# USB-SERIAL.net
KiCad netlist of a schematic drawn in Altium Designer
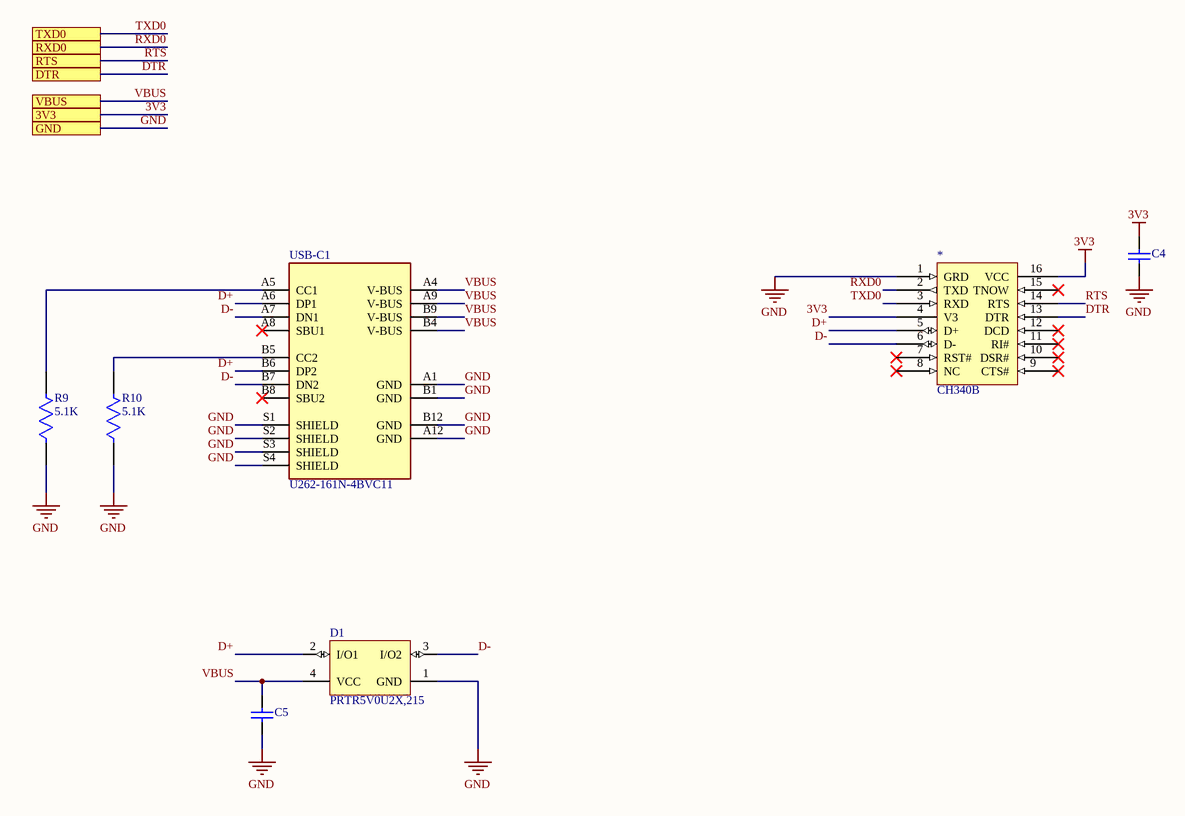
[diagram p0: USB-SERIAL.SchDoc]

(export (version "E")
  (design (tool "Eeschema 10.0.6"))
  (components
    (comp (ref "*")
      (value "CH340B")
      (footprint "CH340B")
      (description "- USB 2.0 Transceiver 2Mbps SOP-16_150mil USB ICs ROHS")
      (libsource (lib "Isidro_Library") (part "CH340B"))
    )
    (comp (ref "C4")
      (value "08055C104KAT2A")
      (footprint "CAPC2013X94X50ML20T25")
      (description "Chip Capacitor, Ceramic, 0.1 uF, 10%, 50 V, 0805, RoHS, Tape and Reel")
      (fields (field (name "MANUFACTURER") "AVX"))
      (libsource (lib "Altium Content Vault") (part "CAP-NP-2"))
    )
    (comp (ref "C5")
      (value "08055C104KAT2A")
      (footprint "CAPC2013X94X50ML20T25")
      (description "Chip Capacitor, Ceramic, 0.1 uF, 10%, 50 V, 0805, RoHS, Tape and Reel")
      (fields (field (name "MANUFACTURER") "AVX"))
      (libsource (lib "Altium Content Vault") (part "CAP-NP-2"))
    )
    (comp (ref "D1")
      (value "PRTR5V0U2X,215")
      (footprint "NXP-SOT143B-4_V")
      (fields (field (name "MANUFACTURER") "NXP Semiconductors"))
      (libsource (lib "Altium Content Vault") (part "NXP-PRTR5V0U2X,215-4"))
    )
    (comp (ref "R9")
      (value "5.1K")
      (footprint "FP-CRCW0805-e3-MFG")
      (description "RES Thick Film, 5.1kΩ, 1%, 0.125W, 100ppm/°C, 0805")
      (fields (field (name "TOLERANCE") "1%"))
      (libsource (lib "Altium Content Vault") (part "1029c3af85768c4190bb7ad29bc67b5"))
    )
    (comp (ref "R10")
      (value "5.1K")
      (footprint "FP-CRCW0805-e3-MFG")
      (description "RES Thick Film, 5.1kΩ, 1%, 0.125W, 100ppm/°C, 0805")
      (fields (field (name "TOLERANCE") "1%"))
      (libsource (lib "Altium Content Vault") (part "1029c3af85768c4190bb7ad29bc67b5"))
    )
    (comp (ref "USB-C1")
      (value "U262-161N-4BVC11")
      (footprint "U262-161N-4BVC11")
      (description "USB - Type C Female 16 SMT USB Connectors RoHS")
      (libsource (lib "AQIMon") (part "U262-161N-4BVC11"))
    )
  )
  (nets
    (net (code "1") (name "/D+") (class "Default")
      (node (ref "*") (pin "5") (pinfunction "D+_5") (pintype "bidirectional"))
      (node (ref "D1") (pin "2") (pinfunction "I/O1_2") (pintype "bidirectional"))
      (node (ref "USB-C1") (pin "A6") (pinfunction "DP1_A6") (pintype "power_in"))
      (node (ref "USB-C1") (pin "B6") (pinfunction "DP2_B6") (pintype "power_in"))
    )
    (net (code "2") (name "/D-") (class "Default")
      (node (ref "*") (pin "6") (pinfunction "D-_6") (pintype "bidirectional"))
      (node (ref "D1") (pin "3") (pinfunction "I/O2_3") (pintype "bidirectional"))
      (node (ref "USB-C1") (pin "A7") (pinfunction "DN1_A7") (pintype "power_in"))
      (node (ref "USB-C1") (pin "B7") (pinfunction "DN2_B7") (pintype "power_in"))
    )
    (net (code "3") (name "/DTR") (class "Default")
      (node (ref "*") (pin "13") (pinfunction "DTR_13") (pintype "input"))
    )
    (net (code "4") (name "/RTS") (class "Default")
      (node (ref "*") (pin "14") (pinfunction "RTS_14") (pintype "input"))
    )
    (net (code "5") (name "/RXD0") (class "Default")
      (node (ref "*") (pin "2") (pinfunction "TXD_2") (pintype "output"))
    )
    (net (code "6") (name "/TXD0") (class "Default")
      (node (ref "*") (pin "3") (pinfunction "RXD_3") (pintype "input"))
    )
    (net (code "7") (name "/VBUS") (class "Default")
      (node (ref "C5") (pin "2") (pinfunction "2_2") (pintype "passive"))
      (node (ref "D1") (pin "4") (pinfunction "VCC_4") (pintype "power_in"))
      (node (ref "USB-C1") (pin "A4") (pinfunction "V-BUS_A4") (pintype "power_in"))
      (node (ref "USB-C1") (pin "A9") (pinfunction "V-BUS_A9") (pintype "power_in"))
      (node (ref "USB-C1") (pin "B4") (pinfunction "V-BUS_B4") (pintype "power_in"))
      (node (ref "USB-C1") (pin "B9") (pinfunction "V-BUS_B9") (pintype "power_in"))
    )
    (net (code "8") (name "3V3") (class "Default")
      (node (ref "*") (pin "16") (pinfunction "VCC_16") (pintype "power_in"))
      (node (ref "*") (pin "4") (pinfunction "V3_4") (pintype "power_in"))
      (node (ref "C4") (pin "2") (pinfunction "2_2") (pintype "passive"))
    )
    (net (code "9") (name "GND") (class "Default")
      (node (ref "*") (pin "1") (pinfunction "GRD_1") (pintype "input"))
      (node (ref "C4") (pin "1") (pinfunction "1_1") (pintype "passive"))
      (node (ref "C5") (pin "1") (pinfunction "1_1") (pintype "passive"))
      (node (ref "D1") (pin "1") (pinfunction "GND_1") (pintype "power_in"))
      (node (ref "R10") (pin "1") (pinfunction "1_1") (pintype "passive"))
      (node (ref "R9") (pin "1") (pinfunction "1_1") (pintype "passive"))
      (node (ref "USB-C1") (pin "A1") (pinfunction "GND_A1") (pintype "power_in"))
      (node (ref "USB-C1") (pin "A12") (pinfunction "GND_A12") (pintype "power_in"))
      (node (ref "USB-C1") (pin "B1") (pinfunction "GND_B1") (pintype "power_in"))
      (node (ref "USB-C1") (pin "B12") (pinfunction "GND_B12") (pintype "power_in"))
      (node (ref "USB-C1") (pin "S1") (pinfunction "SHIELD_S1") (pintype "passive"))
      (node (ref "USB-C1") (pin "S2") (pinfunction "SHIELD_S2") (pintype "passive"))
      (node (ref "USB-C1") (pin "S3") (pinfunction "SHIELD_S3") (pintype "passive"))
      (node (ref "USB-C1") (pin "S4") (pinfunction "SHIELD_S4") (pintype "passive"))
    )
    (net (code "10") (name "Net-(USB-C1-CC1)") (class "Default")
      (node (ref "R9") (pin "2") (pinfunction "2_2") (pintype "passive"))
      (node (ref "USB-C1") (pin "A5") (pinfunction "CC1_A5") (pintype "power_in"))
    )
    (net (code "11") (name "Net-(USB-C1-CC2)") (class "Default")
      (node (ref "R10") (pin "2") (pinfunction "2_2") (pintype "passive"))
      (node (ref "USB-C1") (pin "B5") (pinfunction "CC2_B5") (pintype "power_in"))
    )
    (net (code "12") (name "unconnected-(*-CTS#-Pad9)") (class "Default")
      (node (ref "*") (pin "9") (pinfunction "CTS#_9") (pintype "input+no_connect"))
    )
    (net (code "13") (name "unconnected-(*-DCD-Pad12)") (class "Default")
      (node (ref "*") (pin "12") (pinfunction "DCD_12") (pintype "input+no_connect"))
    )
    (net (code "14") (name "unconnected-(*-DSR#-Pad10)") (class "Default")
      (node (ref "*") (pin "10") (pinfunction "DSR#_10") (pintype "input+no_connect"))
    )
    (net (code "15") (name "unconnected-(*-NC-Pad8)") (class "Default")
      (node (ref "*") (pin "8") (pinfunction "NC_8") (pintype "input+no_connect"))
    )
    (net (code "16") (name "unconnected-(*-RI#-Pad11)") (class "Default")
      (node (ref "*") (pin "11") (pinfunction "RI#_11") (pintype "input+no_connect"))
    )
    (net (code "17") (name "unconnected-(*-RST#-Pad7)") (class "Default")
      (node (ref "*") (pin "7") (pinfunction "RST#_7") (pintype "input+no_connect"))
    )
    (net (code "18") (name "unconnected-(*-TNOW-Pad15)") (class "Default")
      (node (ref "*") (pin "15") (pinfunction "TNOW_15") (pintype "input+no_connect"))
    )
    (net (code "19") (name "unconnected-(USB-C1-SBU1-PadA8)") (class "Default")
      (node (ref "USB-C1") (pin "A8") (pinfunction "SBU1_A8") (pintype "power_in+no_connect"))
    )
    (net (code "20") (name "unconnected-(USB-C1-SBU2-PadB8)") (class "Default")
      (node (ref "USB-C1") (pin "B8") (pinfunction "SBU2_B8") (pintype "power_in+no_connect"))
    )
  )
)
